# FPGA_Power.net
KiCad netlist of a schematic drawn in Altium Designer
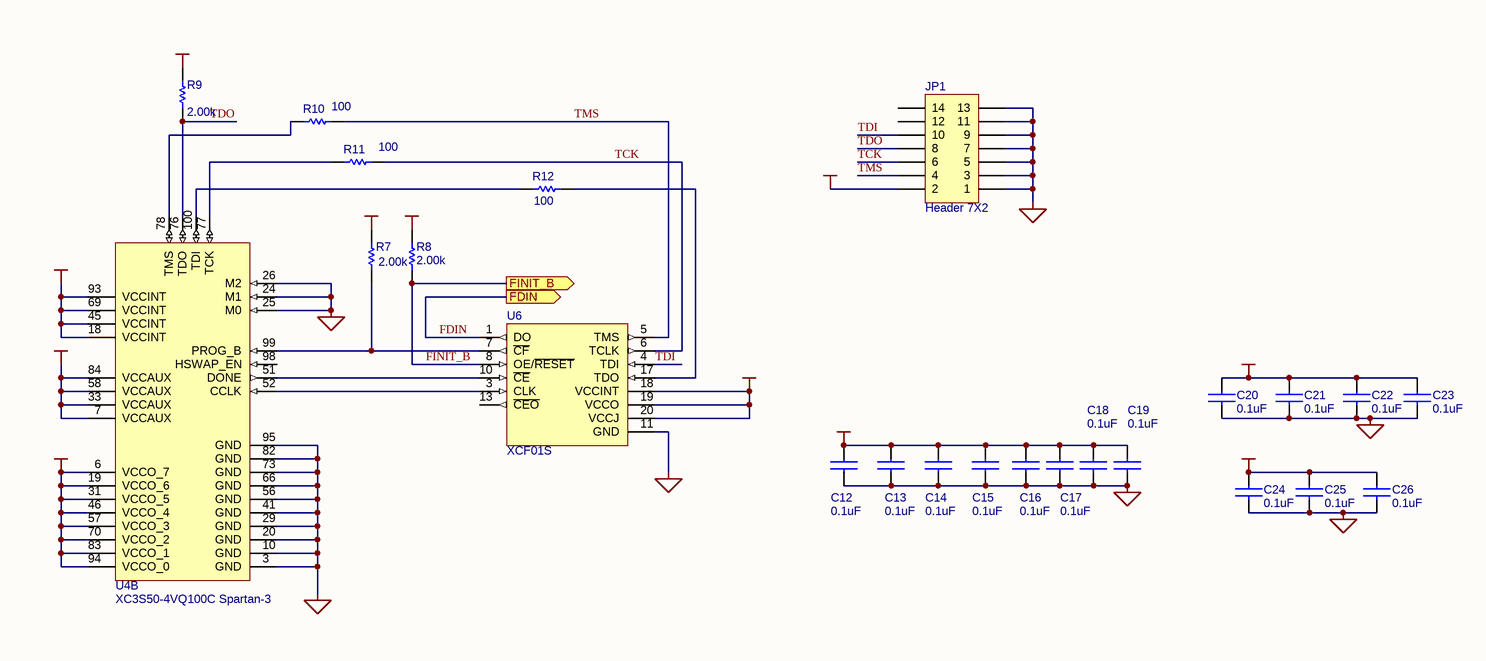
[diagram p0: FPGA Power.SCHDOC]

(export (version "E")
  (design (tool "Eeschema 10.0.6"))
  (components
    (comp (ref "C12")
      (value "0.1uF")
      (footprint "0603")
      (description "Standard Capacitor")
      (fields (field (name "Comment") "CAPACITOR"))
      (libsource (lib "parts") (part "CAPACITOR"))
    )
    (comp (ref "C13")
      (value "0.1uF")
      (footprint "0603")
      (description "Standard Capacitor")
      (fields (field (name "Comment") "CAPACITOR"))
      (libsource (lib "parts") (part "CAPACITOR"))
    )
    (comp (ref "C14")
      (value "0.1uF")
      (footprint "0603")
      (description "Standard Capacitor")
      (fields (field (name "Comment") "CAPACITOR"))
      (libsource (lib "parts") (part "CAPACITOR"))
    )
    (comp (ref "C15")
      (value "0.1uF")
      (footprint "0603")
      (description "Standard Capacitor")
      (fields (field (name "Comment") "CAPACITOR"))
      (libsource (lib "parts") (part "CAPACITOR"))
    )
    (comp (ref "C16")
      (value "0.1uF")
      (footprint "0603")
      (description "Standard Capacitor")
      (fields (field (name "Comment") "CAPACITOR"))
      (libsource (lib "parts") (part "CAPACITOR"))
    )
    (comp (ref "C17")
      (value "0.1uF")
      (footprint "0603")
      (description "Standard Capacitor")
      (fields (field (name "Comment") "CAPACITOR"))
      (libsource (lib "parts") (part "CAPACITOR"))
    )
    (comp (ref "C18")
      (value "0.1uF")
      (footprint "0603")
      (description "Standard Capacitor")
      (fields (field (name "Comment") "CAPACITOR"))
      (libsource (lib "parts") (part "CAPACITOR"))
    )
    (comp (ref "C19")
      (value "0.1uF")
      (footprint "0603")
      (description "Standard Capacitor")
      (fields (field (name "Comment") "CAPACITOR"))
      (libsource (lib "parts") (part "CAPACITOR"))
    )
    (comp (ref "C20")
      (value "0.1uF")
      (footprint "0603")
      (description "Standard Capacitor")
      (fields (field (name "Comment") "CAPACITOR"))
      (libsource (lib "parts") (part "CAPACITOR"))
    )
    (comp (ref "C21")
      (value "0.1uF")
      (footprint "0603")
      (description "Standard Capacitor")
      (fields (field (name "Comment") "CAPACITOR"))
      (libsource (lib "parts") (part "CAPACITOR"))
    )
    (comp (ref "C22")
      (value "0.1uF")
      (footprint "0603")
      (description "Standard Capacitor")
      (fields (field (name "Comment") "CAPACITOR"))
      (libsource (lib "parts") (part "CAPACITOR"))
    )
    (comp (ref "C23")
      (value "0.1uF")
      (footprint "0603")
      (description "Standard Capacitor")
      (fields (field (name "Comment") "CAPACITOR"))
      (libsource (lib "parts") (part "CAPACITOR"))
    )
    (comp (ref "C24")
      (value "0.1uF")
      (footprint "0603")
      (description "Standard Capacitor")
      (fields (field (name "Comment") "CAPACITOR"))
      (libsource (lib "parts") (part "CAPACITOR"))
    )
    (comp (ref "C25")
      (value "0.1uF")
      (footprint "0603")
      (description "Standard Capacitor")
      (fields (field (name "Comment") "CAPACITOR"))
      (libsource (lib "parts") (part "CAPACITOR"))
    )
    (comp (ref "C26")
      (value "0.1uF")
      (footprint "0603")
      (description "Standard Capacitor")
      (fields (field (name "Comment") "CAPACITOR"))
      (libsource (lib "parts") (part "CAPACITOR"))
    )
    (comp (ref "JP1")
      (value "Header 7X2")
      (footprint "HDR2x7-2mm")
      (description "Header, 7-Pin, Dual row")
      (fields (field (name "MANUFACTURER") "Generic Components") (field (name "PUBLISHER") "Altium Limited"))
      (libsource (lib "Miscellaneous Connectors") (part "Header 7X2"))
    )
    (comp (ref "R7")
      (value "2.00k")
      (footprint "0603")
      (description "Standard Passive Resistor")
      (fields (field (name "Comment") "RESISTOR"))
      (libsource (lib "parts") (part "RESISTOR"))
    )
    (comp (ref "R8")
      (value "2.00k")
      (footprint "0603")
      (description "Standard Passive Resistor")
      (fields (field (name "Comment") "RESISTOR"))
      (libsource (lib "parts") (part "RESISTOR"))
    )
    (comp (ref "R9")
      (value "2.00k")
      (footprint "0603")
      (description "Standard Passive Resistor")
      (fields (field (name "Comment") "RESISTOR"))
      (libsource (lib "parts") (part "RESISTOR"))
    )
    (comp (ref "R10")
      (value "100")
      (footprint "0603")
      (description "Standard Passive Resistor")
      (libsource (lib "parts") (part "RESISTOR"))
    )
    (comp (ref "R11")
      (value "100")
      (footprint "0603")
      (description "Standard Passive Resistor")
      (libsource (lib "parts") (part "RESISTOR"))
    )
    (comp (ref "R12")
      (value "100")
      (footprint "0603")
      (description "Standard Passive Resistor")
      (libsource (lib "parts") (part "RESISTOR"))
    )
    (comp (ref "U4")
      (value "XC3S50-4VQ100C Spartan-3")
      (footprint "F-QFP14X14-G100/N")
      (description "Xilinx Spartan-3 VQ100")
      (libsource (lib "parts") (part "XC3S50-4VQ100C"))
    )
    (comp (ref "U6")
      (value "XCF01S")
      (footprint "TSSO6x6-G20/X.3")
      (description "Xilinx Platform Flash")
      (libsource (lib "parts") (part "XCF01S"))
    )
  )
  (nets
    (net (code "1") (name "+1.2VCC") (class "Default")
      (node (ref "C20") (pin "1") (pintype "passive"))
      (node (ref "C21") (pin "1") (pintype "passive"))
      (node (ref "C22") (pin "1") (pintype "passive"))
      (node (ref "C23") (pin "1") (pintype "passive"))
      (node (ref "U4") (pin "18") (pinfunction "VCCINT_18") (pintype "power_in"))
      (node (ref "U4") (pin "45") (pinfunction "VCCINT_45") (pintype "power_in"))
      (node (ref "U4") (pin "69") (pinfunction "VCCINT_69") (pintype "power_in"))
      (node (ref "U4") (pin "93") (pinfunction "VCCINT_93") (pintype "power_in"))
    )
    (net (code "2") (name "+2.5VCC") (class "Default")
      (node (ref "C24") (pin "1") (pintype "passive"))
      (node (ref "C25") (pin "1") (pintype "passive"))
      (node (ref "C26") (pin "1") (pintype "passive"))
      (node (ref "U4") (pin "33") (pinfunction "VCCAUX_33") (pintype "power_in"))
      (node (ref "U4") (pin "58") (pinfunction "VCCAUX_58") (pintype "power_in"))
      (node (ref "U4") (pin "7") (pinfunction "VCCAUX_7") (pintype "power_in"))
      (node (ref "U4") (pin "84") (pinfunction "VCCAUX_84") (pintype "power_in"))
    )
    (net (code "3") (name "/FDIN") (class "Default")
      (node (ref "U6") (pin "1") (pinfunction "DO_1") (pintype "output"))
    )
    (net (code "4") (name "/FINIT_B") (class "Default")
      (node (ref "R8") (pin "1") (pintype "passive"))
      (node (ref "U6") (pin "8") (pinfunction "OE/~{RESET}_8") (pintype "input"))
    )
    (net (code "5") (name "/TCK") (class "Default")
      (node (ref "JP1") (pin "6") (pinfunction "6_6") (pintype "passive"))
      (node (ref "R11") (pin "1") (pintype "passive"))
      (node (ref "U6") (pin "6") (pinfunction "TCLK_6") (pintype "output"))
    )
    (net (code "6") (name "/TDI") (class "Default")
      (node (ref "JP1") (pin "10") (pinfunction "10_10") (pintype "passive"))
      (node (ref "U6") (pin "4") (pinfunction "TDI_4") (pintype "input"))
    )
    (net (code "7") (name "/TDO") (class "Default")
      (node (ref "JP1") (pin "8") (pinfunction "8_8") (pintype "passive"))
      (node (ref "R9") (pin "1") (pintype "passive"))
      (node (ref "U4") (pin "76") (pinfunction "TDO_76") (pintype "bidirectional"))
    )
    (net (code "8") (name "/TMS") (class "Default")
      (node (ref "JP1") (pin "4") (pinfunction "4_4") (pintype "passive"))
      (node (ref "R10") (pin "1") (pintype "passive"))
      (node (ref "U6") (pin "5") (pinfunction "TMS_5") (pintype "output"))
    )
    (net (code "9") (name "GND") (class "Default")
      (node (ref "C12") (pin "2") (pintype "passive"))
      (node (ref "C13") (pin "2") (pintype "passive"))
      (node (ref "C14") (pin "2") (pintype "passive"))
      (node (ref "C15") (pin "2") (pintype "passive"))
      (node (ref "C16") (pin "2") (pintype "passive"))
      (node (ref "C17") (pin "2") (pintype "passive"))
      (node (ref "C18") (pin "2") (pintype "passive"))
      (node (ref "C19") (pin "2") (pintype "passive"))
      (node (ref "C20") (pin "2") (pintype "passive"))
      (node (ref "C21") (pin "2") (pintype "passive"))
      (node (ref "C22") (pin "2") (pintype "passive"))
      (node (ref "C23") (pin "2") (pintype "passive"))
      (node (ref "C24") (pin "2") (pintype "passive"))
      (node (ref "C25") (pin "2") (pintype "passive"))
      (node (ref "C26") (pin "2") (pintype "passive"))
      (node (ref "JP1") (pin "1") (pinfunction "1_1") (pintype "passive"))
      (node (ref "JP1") (pin "11") (pinfunction "11_11") (pintype "passive"))
      (node (ref "JP1") (pin "13") (pinfunction "13_13") (pintype "passive"))
      (node (ref "JP1") (pin "3") (pinfunction "3_3") (pintype "passive"))
      (node (ref "JP1") (pin "5") (pinfunction "5_5") (pintype "passive"))
      (node (ref "JP1") (pin "7") (pinfunction "7_7") (pintype "passive"))
      (node (ref "JP1") (pin "9") (pinfunction "9_9") (pintype "passive"))
      (node (ref "U4") (pin "10") (pinfunction "GND_10") (pintype "power_in"))
      (node (ref "U4") (pin "20") (pinfunction "GND_20") (pintype "power_in"))
      (node (ref "U4") (pin "24") (pinfunction "M1_24") (pintype "input"))
      (node (ref "U4") (pin "25") (pinfunction "M0_25") (pintype "input"))
      (node (ref "U4") (pin "26") (pinfunction "M2_26") (pintype "input"))
      (node (ref "U4") (pin "29") (pinfunction "GND_29") (pintype "power_in"))
      (node (ref "U4") (pin "3") (pinfunction "GND_3") (pintype "power_in"))
      (node (ref "U4") (pin "41") (pinfunction "GND_41") (pintype "power_in"))
      (node (ref "U4") (pin "56") (pinfunction "GND_56") (pintype "power_in"))
      (node (ref "U4") (pin "66") (pinfunction "GND_66") (pintype "power_in"))
      (node (ref "U4") (pin "73") (pinfunction "GND_73") (pintype "power_in"))
      (node (ref "U4") (pin "82") (pinfunction "GND_82") (pintype "power_in"))
      (node (ref "U4") (pin "95") (pinfunction "GND_95") (pintype "power_in"))
      (node (ref "U6") (pin "11") (pinfunction "GND_11") (pintype "power_in"))
    )
    (net (code "10") (name "Net-(U4B-CCLK)") (class "Default")
      (node (ref "U4") (pin "52") (pinfunction "CCLK_52") (pintype "input"))
      (node (ref "U6") (pin "3") (pinfunction "CLK_3") (pintype "input"))
    )
    (net (code "11") (name "Net-(U4B-DONE)") (class "Default")
      (node (ref "U4") (pin "51") (pinfunction "DONE_51") (pintype "output"))
      (node (ref "U6") (pin "10") (pinfunction "~{CE}_10") (pintype "input"))
    )
    (net (code "12") (name "Net-(U4B-PROG_B)") (class "Default")
      (node (ref "R7") (pin "1") (pintype "passive"))
      (node (ref "U4") (pin "99") (pinfunction "PROG_B_99") (pintype "input"))
      (node (ref "U6") (pin "7") (pinfunction "~{CF}_7") (pintype "output"))
    )
    (net (code "13") (name "Net-(U4B-TCK)") (class "Default")
      (node (ref "R11") (pin "2") (pintype "passive"))
      (node (ref "U4") (pin "77") (pinfunction "TCK_77") (pintype "bidirectional"))
    )
    (net (code "14") (name "Net-(U4B-TDI)") (class "Default")
      (node (ref "R12") (pin "2") (pintype "passive"))
      (node (ref "U4") (pin "100") (pinfunction "TDI_100") (pintype "bidirectional"))
    )
    (net (code "15") (name "Net-(U4B-TMS)") (class "Default")
      (node (ref "R10") (pin "2") (pintype "passive"))
      (node (ref "U4") (pin "78") (pinfunction "TMS_78") (pintype "bidirectional"))
    )
    (net (code "16") (name "Net-(U6-TDO)") (class "Default")
      (node (ref "R12") (pin "1") (pintype "passive"))
      (node (ref "U6") (pin "17") (pinfunction "TDO_17") (pintype "input"))
    )
    (net (code "17") (name "VCC") (class "Default")
      (node (ref "C12") (pin "1") (pintype "passive"))
      (node (ref "C13") (pin "1") (pintype "passive"))
      (node (ref "C14") (pin "1") (pintype "passive"))
      (node (ref "C15") (pin "1") (pintype "passive"))
      (node (ref "C16") (pin "1") (pintype "passive"))
      (node (ref "C17") (pin "1") (pintype "passive"))
      (node (ref "C18") (pin "1") (pintype "passive"))
      (node (ref "C19") (pin "1") (pintype "passive"))
      (node (ref "JP1") (pin "2") (pinfunction "2_2") (pintype "passive"))
      (node (ref "R7") (pin "2") (pintype "passive"))
      (node (ref "R8") (pin "2") (pintype "passive"))
      (node (ref "R9") (pin "2") (pintype "passive"))
      (node (ref "U4") (pin "19") (pinfunction "VCCO_6_19") (pintype "power_in"))
      (node (ref "U4") (pin "31") (pinfunction "VCCO_5_31") (pintype "power_in"))
      (node (ref "U4") (pin "46") (pinfunction "VCCO_4_46") (pintype "power_in"))
      (node (ref "U4") (pin "57") (pinfunction "VCCO_3_57") (pintype "power_in"))
      (node (ref "U4") (pin "6") (pinfunction "VCCO_7_6") (pintype "power_in"))
      (node (ref "U4") (pin "70") (pinfunction "VCCO_2_70") (pintype "power_in"))
      (node (ref "U4") (pin "83") (pinfunction "VCCO_1_83") (pintype "power_in"))
      (node (ref "U4") (pin "94") (pinfunction "VCCO_0_94") (pintype "power_in"))
      (node (ref "U6") (pin "18") (pinfunction "VCCINT_18") (pintype "power_in"))
      (node (ref "U6") (pin "19") (pinfunction "VCCO_19") (pintype "power_in"))
      (node (ref "U6") (pin "20") (pinfunction "VCCJ_20") (pintype "power_in"))
    )
    (net (code "18") (name "unconnected-(JP1-Pad12)") (class "Default")
      (node (ref "JP1") (pin "12") (pinfunction "12_12") (pintype "passive"))
    )
    (net (code "19") (name "unconnected-(JP1-Pad14)") (class "Default")
      (node (ref "JP1") (pin "14") (pinfunction "14_14") (pintype "passive"))
    )
    (net (code "20") (name "unconnected-(U4B-HSWAP_EN-Pad98)") (class "Default")
      (node (ref "U4") (pin "98") (pinfunction "HSWAP_EN_98") (pintype "input"))
    )
    (net (code "21") (name "unconnected-(U6-~{CEO}-Pad13)") (class "Default")
      (node (ref "U6") (pin "13") (pinfunction "~{CEO}_13") (pintype "output"))
    )
  )
)
